# Encoder.net
KiCad netlist of a schematic drawn in EAGLE
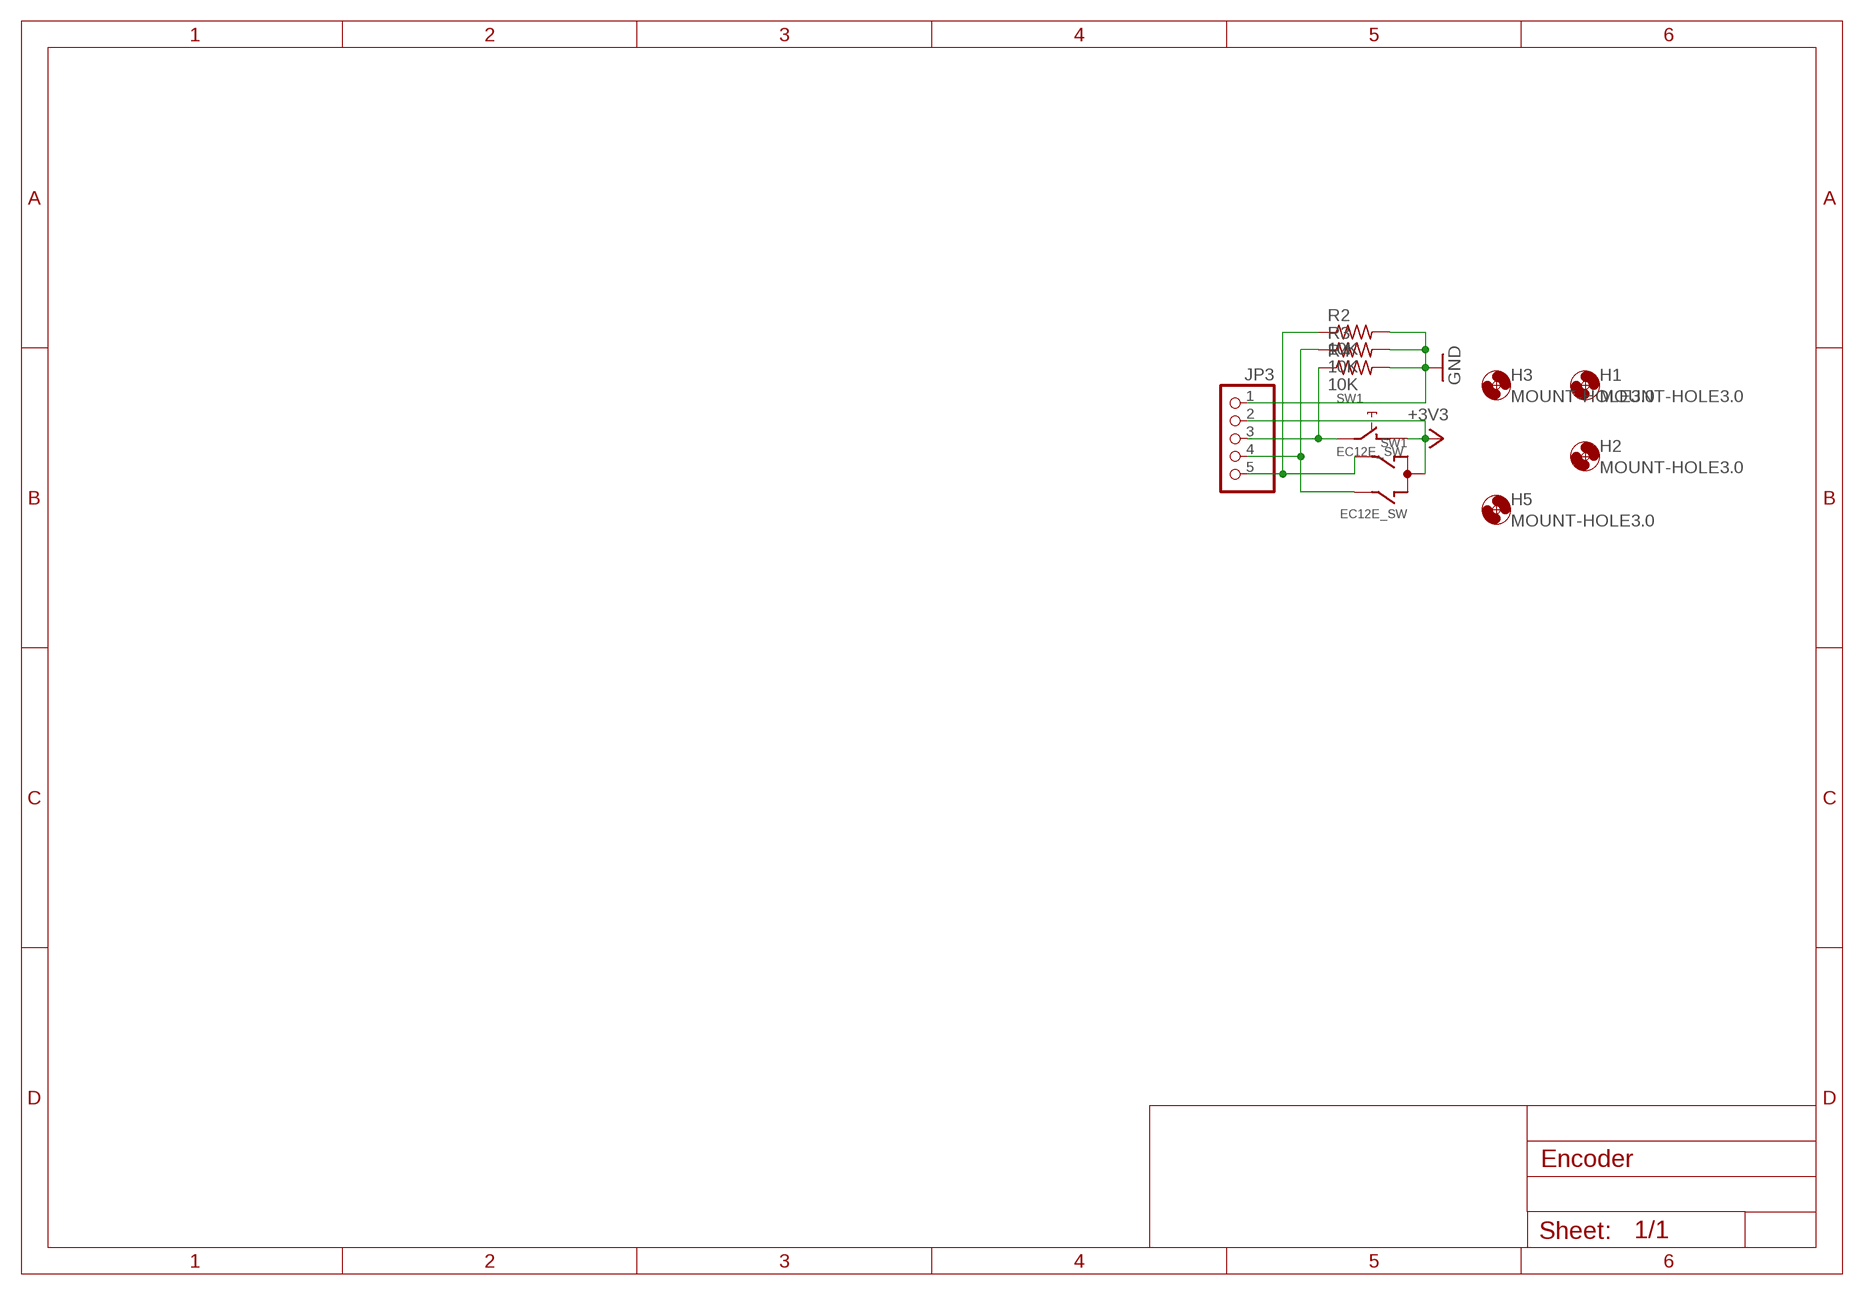
[diagram p0: schematic, sheet 1]

(export (version "E")
  (design (tool "Eeschema 10.0.6"))
  (components
    (comp (ref "H1")
      (value "MOUNT-HOLE3.0")
      (footprint "eagle-import:3,0")
      (libsource (lib "eagle-import") (part "MOUNT-HOLE3.0"))
    )
    (comp (ref "H2")
      (value "MOUNT-HOLE3.0")
      (footprint "eagle-import:3,0")
      (libsource (lib "eagle-import") (part "MOUNT-HOLE3.0"))
    )
    (comp (ref "H3")
      (value "MOUNT-HOLE3.0")
      (footprint "eagle-import:3,0")
      (libsource (lib "eagle-import") (part "MOUNT-HOLE3.0"))
    )
    (comp (ref "H5")
      (value "MOUNT-HOLE3.0")
      (footprint "eagle-import:3,0")
      (libsource (lib "eagle-import") (part "MOUNT-HOLE3.0"))
    )
    (comp (ref "JP3")
      (value "PINHD-1X5")
      (footprint "eagle-import:1X05")
      (libsource (lib "eagle-import") (part "PINHD-1X5"))
    )
    (comp (ref "R2")
      (value "10K")
      (footprint "eagle-import:R0805")
      (libsource (lib "eagle-import") (part "R-US_R0805"))
    )
    (comp (ref "R3")
      (value "10K")
      (footprint "eagle-import:R0805")
      (libsource (lib "eagle-import") (part "R-US_R0805"))
    )
    (comp (ref "R4")
      (value "10K")
      (footprint "eagle-import:R0805")
      (libsource (lib "eagle-import") (part "R-US_R0805"))
    )
    (comp (ref "SW1")
      (value "EC12E_SW")
      (footprint "eagle-import:ALPS_EC12E_SW")
      (fields (field (name "MPN") "EC12E2424407"))
      (libsource (lib "eagle-import") (part "EC12E_SW"))
    )
  )
  (nets
    (net (code "1") (name "+3V3") (class "Default")
      (node (ref "JP3") (pin "2") (pinfunction "2_2") (pintype "passive"))
      (node (ref "SW1") (pin "C") (pinfunction "C_C") (pintype "passive"))
      (node (ref "SW1") (pin "D") (pinfunction "1_D") (pintype "passive"))
    )
    (net (code "2") (name "GND") (class "Default")
      (node (ref "JP3") (pin "1") (pinfunction "1_1") (pintype "passive"))
      (node (ref "R2") (pin "2") (pinfunction "2_2") (pintype "passive"))
      (node (ref "R3") (pin "2") (pinfunction "2_2") (pintype "passive"))
      (node (ref "R4") (pin "2") (pinfunction "2_2") (pintype "passive"))
    )
    (net (code "3") (name "Net-(JP3-Pad4)") (class "Default")
      (node (ref "JP3") (pin "4") (pinfunction "4_4") (pintype "passive"))
      (node (ref "R3") (pin "1") (pinfunction "1_1") (pintype "passive"))
      (node (ref "SW1") (pin "B") (pinfunction "B_B") (pintype "passive"))
    )
    (net (code "4") (name "Net-(JP3-Pad5)") (class "Default")
      (node (ref "JP3") (pin "5") (pinfunction "5_5") (pintype "passive"))
      (node (ref "R2") (pin "1") (pinfunction "1_1") (pintype "passive"))
      (node (ref "SW1") (pin "A") (pinfunction "A_A") (pintype "passive"))
    )
    (net (code "5") (name "Net-(SW1B-2)") (class "Default")
      (node (ref "JP3") (pin "3") (pinfunction "3_3") (pintype "passive"))
      (node (ref "R4") (pin "1") (pinfunction "1_1") (pintype "passive"))
      (node (ref "SW1") (pin "E") (pinfunction "2_E") (pintype "passive"))
    )
  )
)
